# HCRT_STM32F103C8T6_Sch.net
KiCad netlist of a schematic drawn in Altium Designer
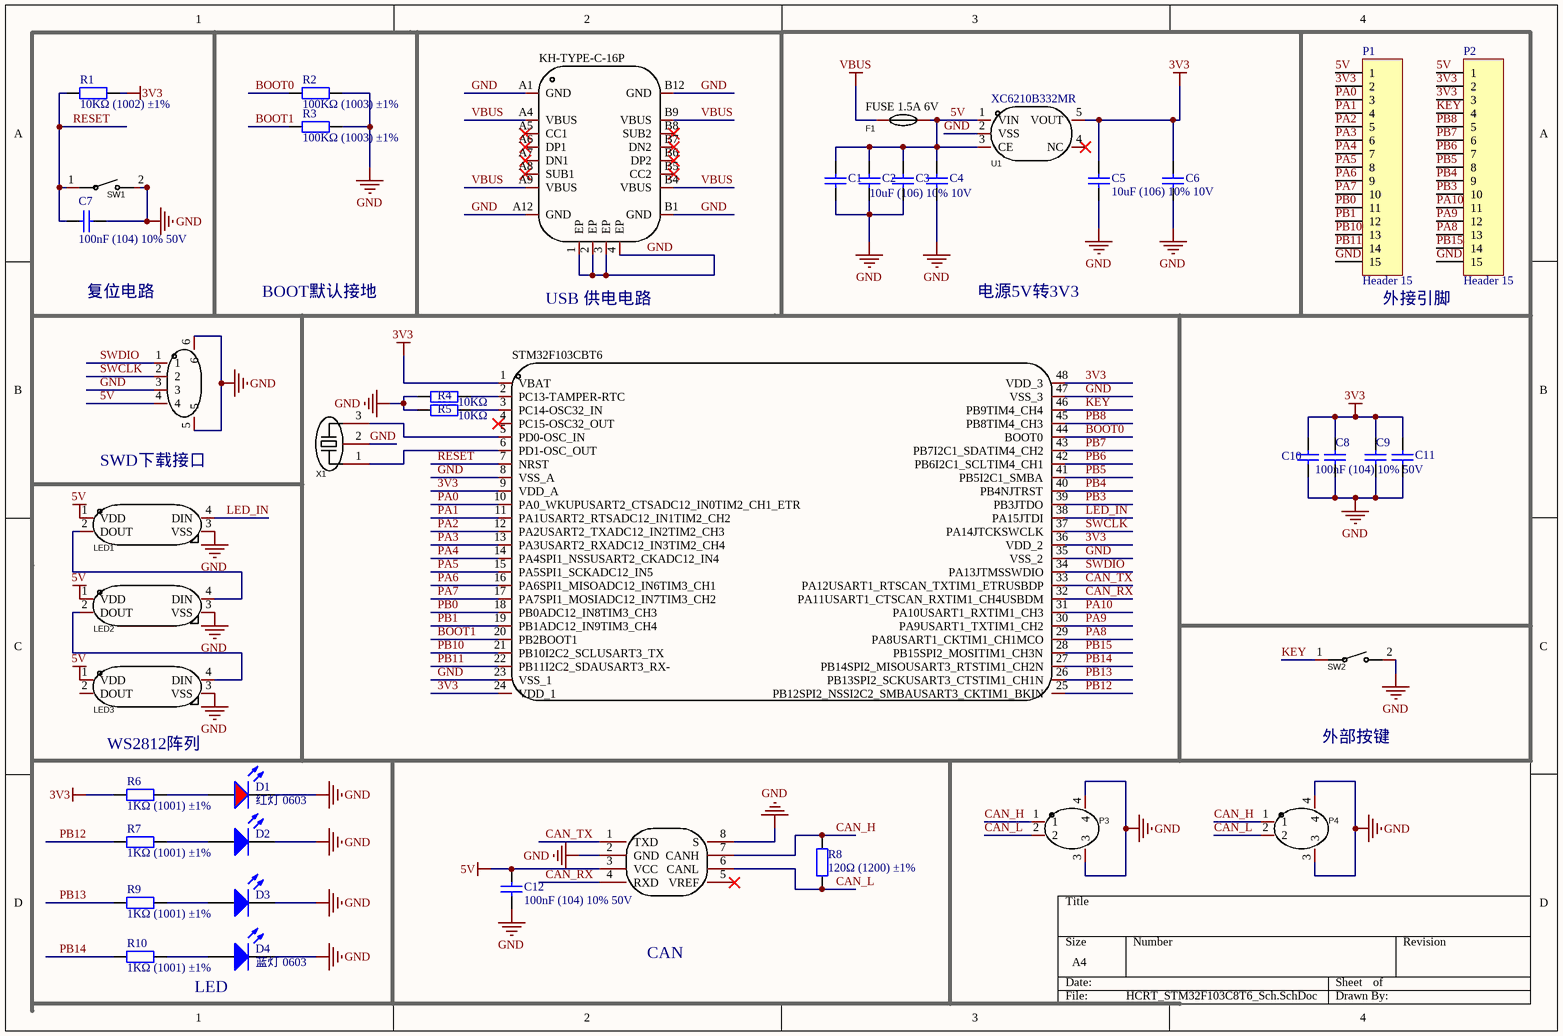
[diagram p0: HCRT_STM32F103C8T6_Sch.SchDoc]

(export (version "E")
  (design (tool "Eeschema 10.0.6"))
  (components
    (comp (ref "C1")
      (value "10uF (106) 10% 10V")
      (footprint "0603_C")
      (description "贴片电容")
      (libsource (lib "Miscellaneous Devices LC") (part "0603 10uF (106) 10% 10V"))
    )
    (comp (ref "C2")
      (value "10uF (106) 10% 10V")
      (footprint "0603_C")
      (description "贴片电容")
      (libsource (lib "Miscellaneous Devices LC") (part "0603 10uF (106) 10% 10V"))
    )
    (comp (ref "C3")
      (value "10uF (106) 10% 10V")
      (footprint "0603_C")
      (description "贴片电容")
      (libsource (lib "Miscellaneous Devices LC") (part "0603 10uF (106) 10% 10V"))
    )
    (comp (ref "C4")
      (value "10uF (106) 10% 10V")
      (footprint "0603_C")
      (description "贴片电容")
      (libsource (lib "Miscellaneous Devices LC") (part "0603 10uF (106) 10% 10V"))
    )
    (comp (ref "C5")
      (value "10uF (106) 10% 10V")
      (footprint "0603_C")
      (description "贴片电容")
      (libsource (lib "Miscellaneous Devices LC") (part "0603 10uF (106) 10% 10V"))
    )
    (comp (ref "C6")
      (value "10uF (106) 10% 10V")
      (footprint "0603_C")
      (description "贴片电容")
      (libsource (lib "Miscellaneous Devices LC") (part "0603 10uF (106) 10% 10V"))
    )
    (comp (ref "C7")
      (value "100nF (104) 10% 50V")
      (footprint "0603_C")
      (description "贴片电容")
      (libsource (lib "Miscellaneous Devices LC") (part "0603 100nF (104) 10% 50V"))
    )
    (comp (ref "C8")
      (value "100nF (104) 10% 50V")
      (footprint "0603_C")
      (description "贴片电容")
      (libsource (lib "Miscellaneous Devices LC") (part "0603 100nF (104) 10% 50V"))
    )
    (comp (ref "C9")
      (value "100nF (104) 10% 50V")
      (footprint "0603_C")
      (description "贴片电容")
      (libsource (lib "Miscellaneous Devices LC") (part "0603 100nF (104) 10% 50V"))
    )
    (comp (ref "C10")
      (value "100nF (104) 10% 50V")
      (footprint "0603_C")
      (description "贴片电容")
      (libsource (lib "Miscellaneous Devices LC") (part "0603 100nF (104) 10% 50V"))
    )
    (comp (ref "C11")
      (value "100nF (104) 10% 50V")
      (footprint "0603_C")
      (description "贴片电容")
      (libsource (lib "Miscellaneous Devices LC") (part "0603 100nF (104) 10% 50V"))
    )
    (comp (ref "C12")
      (value "100nF (104) 10% 50V")
      (footprint "0603_C")
      (description "贴片电容")
      (libsource (lib "Miscellaneous Devices LC") (part "0603 100nF (104) 10% 50V"))
    )
    (comp (ref "CN1")
      (value "HC-1.25-4PWT")
      (footprint "CONN-SMD_4P-P1.25-HC-1.25-4PWT")
      (fields (field (name "MANUFACTURER") "HCTL(华灿天禄)"))
      (libsource (lib "zxy's_LIB") (part "HC-1.25-4PWT"))
    )
    (comp (ref "D1")
      (value "红灯 0603")
      (footprint "0603_LED_S1")
      (description "发光二极管")
      (libsource (lib "Miscellaneous Devices LC") (part "0603 红灯"))
    )
    (comp (ref "D2")
      (value "蓝灯 0603")
      (footprint "0603_LED_S1")
      (description "发光二极管")
      (libsource (lib "Miscellaneous Devices LC") (part "0603 蓝灯"))
    )
    (comp (ref "D3")
      (value "蓝灯 0603")
      (footprint "0603_LED_S1")
      (description "发光二极管")
      (libsource (lib "Miscellaneous Devices LC") (part "0603 蓝灯"))
    )
    (comp (ref "D4")
      (value "蓝灯 0603")
      (footprint "0603_LED_S1")
      (description "发光二极管")
      (libsource (lib "Miscellaneous Devices LC") (part "0603 蓝灯"))
    )
    (comp (ref "F1")
      (value "FUSE0603")
      (footprint "F0603")
      (fields (field (name "MANUFACTURER") "BHFUSE(佰宏)") (field (name "MANUFACTURER PART") "BSMD0603L-150"))
      (libsource (lib "zxy's_LIB") (part "FUSE0603"))
    )
    (comp (ref "LED1")
      (value "WS2812C")
      (footprint "LED-SMD_4P-L5.0-W5.0-LS5.4-TL-1")
      (fields (field (name "MANUFACTURER") "worldsemi"))
      (libsource (lib "zxy's_LIB") (part "WS2812C"))
    )
    (comp (ref "LED2")
      (value "WS2812C")
      (footprint "LED-SMD_4P-L5.0-W5.0-LS5.4-TL-1")
      (fields (field (name "MANUFACTURER") "worldsemi"))
      (libsource (lib "zxy's_LIB") (part "WS2812C"))
    )
    (comp (ref "LED3")
      (value "WS2812C")
      (footprint "LED-SMD_4P-L5.0-W5.0-LS5.4-TL-1")
      (fields (field (name "MANUFACTURER") "worldsemi"))
      (libsource (lib "zxy's_LIB") (part "WS2812C"))
    )
    (comp (ref "P1")
      (value "Header 15")
      (footprint "HDR1X15")
      (description "Header, 15-Pin")
      (fields (field (name "PUBLISHER") "Altium Limited"))
      (libsource (lib "Miscellaneous Connectors") (part "Header 15"))
    )
    (comp (ref "P2")
      (value "Header 15")
      (footprint "HDR1X15")
      (description "Header, 15-Pin")
      (fields (field (name "PUBLISHER") "Altium Limited"))
      (libsource (lib "Miscellaneous Connectors") (part "Header 15"))
    )
    (comp (ref "P3")
      (value "1.25_2P")
      (footprint "CONN-SMD_SM02B-GHS-TB-LF-SN")
      (fields (field (name "MANUFACTURER") "JST") (field (name "MANUFACTURER PART") "SM02B-GHS-TB(LF)(SN)"))
      (libsource (lib "zxy's_LIB") (part "1.25_2P"))
    )
    (comp (ref "P4")
      (value "1.25_2P")
      (footprint "CONN-SMD_SM02B-GHS-TB-LF-SN")
      (fields (field (name "MANUFACTURER") "JST") (field (name "MANUFACTURER PART") "SM02B-GHS-TB(LF)(SN)"))
      (libsource (lib "zxy's_LIB") (part "1.25_2P"))
    )
    (comp (ref "R1")
      (value "10KΩ (1002) ±1%")
      (footprint "0603_R")
      (description "贴片电阻")
      (libsource (lib "Miscellaneous Devices LC") (part "0603 10KΩ (1002) 1%"))
    )
    (comp (ref "R2")
      (value "100KΩ (1003) ±1%")
      (footprint "0603_R")
      (description "贴片电阻")
      (libsource (lib "Miscellaneous Devices LC") (part "0603 100KΩ (1003) 1%"))
    )
    (comp (ref "R3")
      (value "100KΩ (1003) ±1%")
      (footprint "0603_R")
      (description "贴片电阻")
      (libsource (lib "Miscellaneous Devices LC") (part "0603 100KΩ (1003) 1%"))
    )
    (comp (ref "R4")
      (value "10KΩ")
      (footprint "0603_R")
      (description "贴片电阻")
      (libsource (lib "Miscellaneous Devices LC") (part "0603 10KΩ (1002) 1%"))
    )
    (comp (ref "R5")
      (value "10KΩ")
      (footprint "0603_R")
      (description "贴片电阻")
      (libsource (lib "Miscellaneous Devices LC") (part "0603 10KΩ (1002) 1%"))
    )
    (comp (ref "R6")
      (value "1KΩ (1001) ±1%")
      (footprint "0603_R")
      (description "贴片电阻")
      (libsource (lib "Miscellaneous Devices LC") (part "0603 1KΩ (1001) 1%"))
    )
    (comp (ref "R7")
      (value "1KΩ (1001) ±1%")
      (footprint "0603_R")
      (description "贴片电阻")
      (libsource (lib "Miscellaneous Devices LC") (part "0603 1KΩ (1001) 1%"))
    )
    (comp (ref "R8")
      (value "120Ω (1200) ±1%")
      (footprint "0603_R")
      (description "贴片电阻")
      (libsource (lib "Miscellaneous Devices LC") (part "0603 120Ω (1200) 1%"))
    )
    (comp (ref "R9")
      (value "1KΩ (1001) ±1%")
      (footprint "0603_R")
      (description "贴片电阻")
      (libsource (lib "Miscellaneous Devices LC") (part "0603 1KΩ (1001) 1%"))
    )
    (comp (ref "R10")
      (value "1KΩ (1001) ±1%")
      (footprint "0603_R")
      (description "贴片电阻")
      (libsource (lib "Miscellaneous Devices LC") (part "0603 1KΩ (1001) 1%"))
    )
    (comp (ref "SW1")
      (value "K2-1107ST-A4DW-06_C118141")
      (footprint "KEY-SMD_L6.2-W3.6-LS8.0")
      (fields (field (name "MANUFACTURER") "韩国韩荣") (field (name "MANUFACTURER PART") "K2-1107ST-A4DW-06"))
      (libsource (lib "zxy's_LIB") (part "K2-1107ST-A4DW-06_C118141"))
    )
    (comp (ref "SW2")
      (value "K2-1107ST-A4DW-06_C118141")
      (footprint "KEY-SMD_L6.2-W3.6-LS8.0")
      (fields (field (name "MANUFACTURER") "韩国韩荣") (field (name "MANUFACTURER PART") "K2-1107ST-A4DW-06"))
      (libsource (lib "zxy's_LIB") (part "K2-1107ST-A4DW-06_C118141"))
    )
    (comp (ref "U1")
      (value "XC6210B332MR")
      (footprint "SOT-23-5_L3.0-W1.7-P0.95-LS2.8-BR")
      (fields (field (name "MANUFACTURER") "TOREX(特瑞仕)"))
      (libsource (lib "zxy's_LIB") (part "XC6210B332MR"))
    )
    (comp (ref "U2")
      (value "STM32F103CBT6")
      (footprint "LQFP-48_L7.0-W7.0-P0.50-LS9.0-BL")
      (fields (field (name "MANUFACTURER") "ST(意法半导体)"))
      (libsource (lib "zxy's_LIB") (part "STM32F103CBT6"))
    )
    (comp (ref "U3")
      (value "TJA1050T/CM,118")
      (footprint "SOIC-8_L5.0-W4.0-P1.27-LS6.0-BL")
      (fields (field (name "MANUFACTURER") "NXP(恩智浦)"))
      (libsource (lib "zxy's_LIB") (part "TJA1050T/CM,118"))
    )
    (comp (ref "USB1")
      (value "KH-TYPE-C-16P")
      (footprint "USB-C-SMD_KH-TYPE-C-16P")
      (fields (field (name "MANUFACTURER") "kinghelm(金航标)"))
      (libsource (lib "zxy's_LIB") (part "KH-TYPE-C-16P"))
    )
    (comp (ref "X1")
      (value "CSTCE8M00G15C99-R0")
      (footprint "OSC-SMD_3P-L3.2-W1.3-P1.2-L")
      (fields (field (name "MANUFACTURER") "muRata(村田)"))
      (libsource (lib "zxy's_LIB") (part "CSTCE8M00G15C99-R0"))
    )
  )
  (nets
    (net (code "1") (name "/BOOT0") (class "Default")
      (node (ref "R2") (pin "1") (pinfunction "1_1") (pintype "passive"))
      (node (ref "U2") (pin "44") (pinfunction "BOOT0_44") (pintype "passive"))
    )
    (net (code "2") (name "/BOOT1") (class "Default")
      (node (ref "R3") (pin "1") (pinfunction "1_1") (pintype "passive"))
      (node (ref "U2") (pin "20") (pinfunction "PB2BOOT1_20") (pintype "passive"))
    )
    (net (code "3") (name "/CAN_H") (class "Default")
      (node (ref "P3") (pin "1") (pinfunction "1_1") (pintype "passive"))
      (node (ref "P4") (pin "1") (pinfunction "1_1") (pintype "passive"))
      (node (ref "R8") (pin "2") (pinfunction "2_2") (pintype "passive"))
      (node (ref "U3") (pin "7") (pinfunction "CANH_7") (pintype "passive"))
    )
    (net (code "4") (name "/CAN_L") (class "Default")
      (node (ref "P3") (pin "2") (pinfunction "2_2") (pintype "passive"))
      (node (ref "P4") (pin "2") (pinfunction "2_2") (pintype "passive"))
      (node (ref "R8") (pin "1") (pinfunction "1_1") (pintype "passive"))
      (node (ref "U3") (pin "6") (pinfunction "CANL_6") (pintype "passive"))
    )
    (net (code "5") (name "/CAN_RX") (class "Default")
      (node (ref "U2") (pin "32") (pinfunction "PA11USART1_CTSCAN_RXTIM1_CH4USBDM_32") (pintype "passive"))
      (node (ref "U3") (pin "4") (pinfunction "RXD_4") (pintype "passive"))
    )
    (net (code "6") (name "/CAN_TX") (class "Default")
      (node (ref "U2") (pin "33") (pinfunction "PA12USART1_RTSCAN_TXTIM1_ETRUSBDP_33") (pintype "passive"))
      (node (ref "U3") (pin "1") (pinfunction "TXD_1") (pintype "passive"))
    )
    (net (code "7") (name "/KEY") (class "Default")
      (node (ref "P2") (pin "4") (pinfunction "4_4") (pintype "passive"))
      (node (ref "SW2") (pin "1") (pinfunction "1_1") (pintype "passive"))
      (node (ref "U2") (pin "46") (pinfunction "PB9TIM4_CH4_46") (pintype "passive"))
    )
    (net (code "8") (name "/LED_IN") (class "Default")
      (node (ref "LED1") (pin "4") (pinfunction "DIN_4") (pintype "passive"))
      (node (ref "U2") (pin "38") (pinfunction "PA15JTDI_38") (pintype "passive"))
    )
    (net (code "9") (name "/PA0") (class "Default")
      (node (ref "P1") (pin "3") (pinfunction "3_3") (pintype "passive"))
      (node (ref "U2") (pin "10") (pinfunction "PA0_WKUPUSART2_CTSADC12_IN0TIM2_CH1_ETR_10") (pintype "passive"))
    )
    (net (code "10") (name "/PA1") (class "Default")
      (node (ref "P1") (pin "4") (pinfunction "4_4") (pintype "passive"))
      (node (ref "U2") (pin "11") (pinfunction "PA1USART2_RTSADC12_IN1TIM2_CH2_11") (pintype "passive"))
    )
    (net (code "11") (name "/PA2") (class "Default")
      (node (ref "P1") (pin "5") (pinfunction "5_5") (pintype "passive"))
      (node (ref "U2") (pin "12") (pinfunction "PA2USART2_TXADC12_IN2TIM2_CH3_12") (pintype "passive"))
    )
    (net (code "12") (name "/PA3") (class "Default")
      (node (ref "P1") (pin "6") (pinfunction "6_6") (pintype "passive"))
      (node (ref "U2") (pin "13") (pinfunction "PA3USART2_RXADC12_IN3TIM2_CH4_13") (pintype "passive"))
    )
    (net (code "13") (name "/PA4") (class "Default")
      (node (ref "P1") (pin "7") (pinfunction "7_7") (pintype "passive"))
      (node (ref "U2") (pin "14") (pinfunction "PA4SPI1_NSSUSART2_CKADC12_IN4_14") (pintype "passive"))
    )
    (net (code "14") (name "/PA5") (class "Default")
      (node (ref "P1") (pin "8") (pinfunction "8_8") (pintype "passive"))
      (node (ref "U2") (pin "15") (pinfunction "PA5SPI1_SCKADC12_IN5_15") (pintype "passive"))
    )
    (net (code "15") (name "/PA6") (class "Default")
      (node (ref "P1") (pin "9") (pinfunction "9_9") (pintype "passive"))
      (node (ref "U2") (pin "16") (pinfunction "PA6SPI1_MISOADC12_IN6TIM3_CH1_16") (pintype "passive"))
    )
    (net (code "16") (name "/PA7") (class "Default")
      (node (ref "P1") (pin "10") (pinfunction "10_10") (pintype "passive"))
      (node (ref "U2") (pin "17") (pinfunction "PA7SPI1_MOSIADC12_IN7TIM3_CH2_17") (pintype "passive"))
    )
    (net (code "17") (name "/PA8") (class "Default")
      (node (ref "P2") (pin "13") (pinfunction "13_13") (pintype "passive"))
      (node (ref "U2") (pin "29") (pinfunction "PA8USART1_CKTIM1_CH1MCO_29") (pintype "passive"))
    )
    (net (code "18") (name "/PA9") (class "Default")
      (node (ref "P2") (pin "12") (pinfunction "12_12") (pintype "passive"))
      (node (ref "U2") (pin "30") (pinfunction "PA9USART1_TXTIM1_CH2_30") (pintype "passive"))
    )
    (net (code "19") (name "/PA10") (class "Default")
      (node (ref "P2") (pin "11") (pinfunction "11_11") (pintype "passive"))
      (node (ref "U2") (pin "31") (pinfunction "PA10USART1_RXTIM1_CH3_31") (pintype "passive"))
    )
    (net (code "20") (name "/PB0") (class "Default")
      (node (ref "P1") (pin "11") (pinfunction "11_11") (pintype "passive"))
      (node (ref "U2") (pin "18") (pinfunction "PB0ADC12_IN8TIM3_CH3_18") (pintype "passive"))
    )
    (net (code "21") (name "/PB1") (class "Default")
      (node (ref "P1") (pin "12") (pinfunction "12_12") (pintype "passive"))
      (node (ref "U2") (pin "19") (pinfunction "PB1ADC12_IN9TIM3_CH4_19") (pintype "passive"))
    )
    (net (code "22") (name "/PB3") (class "Default")
      (node (ref "P2") (pin "10") (pinfunction "10_10") (pintype "passive"))
      (node (ref "U2") (pin "39") (pinfunction "PB3JTDO_39") (pintype "passive"))
    )
    (net (code "23") (name "/PB4") (class "Default")
      (node (ref "P2") (pin "9") (pinfunction "9_9") (pintype "passive"))
      (node (ref "U2") (pin "40") (pinfunction "PB4NJTRST_40") (pintype "passive"))
    )
    (net (code "24") (name "/PB5") (class "Default")
      (node (ref "P2") (pin "8") (pinfunction "8_8") (pintype "passive"))
      (node (ref "U2") (pin "41") (pinfunction "PB5I2C1_SMBA_41") (pintype "passive"))
    )
    (net (code "25") (name "/PB6") (class "Default")
      (node (ref "P2") (pin "7") (pinfunction "7_7") (pintype "passive"))
      (node (ref "U2") (pin "42") (pinfunction "PB6I2C1_SCLTIM4_CH1_42") (pintype "passive"))
    )
    (net (code "26") (name "/PB7") (class "Default")
      (node (ref "P2") (pin "6") (pinfunction "6_6") (pintype "passive"))
      (node (ref "U2") (pin "43") (pinfunction "PB7I2C1_SDATIM4_CH2_43") (pintype "passive"))
    )
    (net (code "27") (name "/PB8") (class "Default")
      (node (ref "P2") (pin "5") (pinfunction "5_5") (pintype "passive"))
      (node (ref "U2") (pin "45") (pinfunction "PB8TIM4_CH3_45") (pintype "passive"))
    )
    (net (code "28") (name "/PB10") (class "Default")
      (node (ref "P1") (pin "13") (pinfunction "13_13") (pintype "passive"))
      (node (ref "U2") (pin "21") (pinfunction "PB10I2C2_SCLUSART3_TX_21") (pintype "passive"))
    )
    (net (code "29") (name "/PB11") (class "Default")
      (node (ref "P1") (pin "14") (pinfunction "14_14") (pintype "passive"))
      (node (ref "U2") (pin "22") (pinfunction "PB11I2C2_SDAUSART3_RX-_22") (pintype "passive"))
    )
    (net (code "30") (name "/PB12") (class "Default")
      (node (ref "R7") (pin "1") (pinfunction "1_1") (pintype "passive"))
      (node (ref "U2") (pin "25") (pinfunction "PB12SPI2_NSSI2C2_SMBAUSART3_CKTIM1_BKIN_25") (pintype "passive"))
    )
    (net (code "31") (name "/PB13") (class "Default")
      (node (ref "R9") (pin "1") (pinfunction "1_1") (pintype "passive"))
      (node (ref "U2") (pin "26") (pinfunction "PB13SPI2_SCKUSART3_CTSTIM1_CH1N_26") (pintype "passive"))
    )
    (net (code "32") (name "/PB14") (class "Default")
      (node (ref "R10") (pin "1") (pinfunction "1_1") (pintype "passive"))
      (node (ref "U2") (pin "27") (pinfunction "PB14SPI2_MISOUSART3_RTSTIM1_CH2N_27") (pintype "passive"))
    )
    (net (code "33") (name "/PB15") (class "Default")
      (node (ref "P2") (pin "14") (pinfunction "14_14") (pintype "passive"))
      (node (ref "U2") (pin "28") (pinfunction "PB15SPI2_MOSITIM1_CH3N_28") (pintype "passive"))
    )
    (net (code "34") (name "/RESET") (class "Default")
      (node (ref "C7") (pin "1") (pinfunction "1_1") (pintype "passive"))
      (node (ref "R1") (pin "1") (pinfunction "1_1") (pintype "passive"))
      (node (ref "SW1") (pin "1") (pinfunction "1_1") (pintype "passive"))
      (node (ref "U2") (pin "7") (pinfunction "NRST_7") (pintype "passive"))
    )
    (net (code "35") (name "/SWCLK") (class "Default")
      (node (ref "CN1") (pin "2") (pinfunction "2_2") (pintype "passive"))
      (node (ref "U2") (pin "37") (pinfunction "PA14JTCKSWCLK_37") (pintype "passive"))
    )
    (net (code "36") (name "/SWDIO") (class "Default")
      (node (ref "CN1") (pin "1") (pinfunction "1_1") (pintype "passive"))
      (node (ref "U2") (pin "34") (pinfunction "PA13JTMSSWDIO_34") (pintype "passive"))
    )
    (net (code "37") (name "3V3") (class "Default")
      (node (ref "C10") (pin "2") (pinfunction "2_2") (pintype "passive"))
      (node (ref "C11") (pin "2") (pinfunction "2_2") (pintype "passive"))
      (node (ref "C5") (pin "2") (pinfunction "2_2") (pintype "passive"))
      (node (ref "C6") (pin "2") (pinfunction "2_2") (pintype "passive"))
      (node (ref "C8") (pin "2") (pinfunction "2_2") (pintype "passive"))
      (node (ref "C9") (pin "2") (pinfunction "2_2") (pintype "passive"))
      (node (ref "P1") (pin "2") (pinfunction "2_2") (pintype "passive"))
      (node (ref "P2") (pin "2") (pinfunction "2_2") (pintype "passive"))
      (node (ref "P2") (pin "3") (pinfunction "3_3") (pintype "passive"))
      (node (ref "R1") (pin "2") (pinfunction "2_2") (pintype "passive"))
      (node (ref "R6") (pin "1") (pinfunction "1_1") (pintype "passive"))
      (node (ref "U1") (pin "5") (pinfunction "VOUT_5") (pintype "passive"))
      (node (ref "U2") (pin "1") (pinfunction "VBAT_1") (pintype "passive"))
      (node (ref "U2") (pin "24") (pinfunction "VDD_1_24") (pintype "passive"))
      (node (ref "U2") (pin "36") (pinfunction "VDD_2_36") (pintype "passive"))
      (node (ref "U2") (pin "48") (pinfunction "VDD_3_48") (pintype "passive"))
      (node (ref "U2") (pin "9") (pinfunction "VDD_A_9") (pintype "passive"))
    )
    (net (code "38") (name "5V") (class "Default")
      (node (ref "C1") (pin "2") (pinfunction "2_2") (pintype "passive"))
      (node (ref "C12") (pin "2") (pinfunction "2_2") (pintype "passive"))
      (node (ref "C2") (pin "2") (pinfunction "2_2") (pintype "passive"))
      (node (ref "C3") (pin "2") (pinfunction "2_2") (pintype "passive"))
      (node (ref "C4") (pin "2") (pinfunction "2_2") (pintype "passive"))
      (node (ref "CN1") (pin "4") (pinfunction "4_4") (pintype "passive"))
      (node (ref "F1") (pin "2") (pinfunction "2_2") (pintype "passive"))
      (node (ref "LED1") (pin "1") (pinfunction "VDD_1") (pintype "passive"))
      (node (ref "LED2") (pin "1") (pinfunction "VDD_1") (pintype "passive"))
      (node (ref "LED3") (pin "1") (pinfunction "VDD_1") (pintype "passive"))
      (node (ref "P1") (pin "1") (pinfunction "1_1") (pintype "passive"))
      (node (ref "P2") (pin "1") (pinfunction "1_1") (pintype "passive"))
      (node (ref "U1") (pin "1") (pinfunction "VIN_1") (pintype "passive"))
      (node (ref "U1") (pin "3") (pinfunction "CE_3") (pintype "passive"))
      (node (ref "U3") (pin "3") (pinfunction "VCC_3") (pintype "passive"))
    )
    (net (code "39") (name "GND") (class "Default")
      (node (ref "C1") (pin "1") (pinfunction "1_1") (pintype "passive"))
      (node (ref "C10") (pin "1") (pinfunction "1_1") (pintype "passive"))
      (node (ref "C11") (pin "1") (pinfunction "1_1") (pintype "passive"))
      (node (ref "C12") (pin "1") (pinfunction "1_1") (pintype "passive"))
      (node (ref "C2") (pin "1") (pinfunction "1_1") (pintype "passive"))
      (node (ref "C3") (pin "1") (pinfunction "1_1") (pintype "passive"))
      (node (ref "C4") (pin "1") (pinfunction "1_1") (pintype "passive"))
      (node (ref "C5") (pin "1") (pinfunction "1_1") (pintype "passive"))
      (node (ref "C6") (pin "1") (pinfunction "1_1") (pintype "passive"))
      (node (ref "C7") (pin "2") (pinfunction "2_2") (pintype "passive"))
      (node (ref "C8") (pin "1") (pinfunction "1_1") (pintype "passive"))
      (node (ref "C9") (pin "1") (pinfunction "1_1") (pintype "passive"))
      (node (ref "CN1") (pin "3") (pinfunction "3_3") (pintype "passive"))
      (node (ref "CN1") (pin "5") (pinfunction "5_5") (pintype "passive"))
      (node (ref "CN1") (pin "6") (pinfunction "6_6") (pintype "passive"))
      (node (ref "D1") (pin "K") (pinfunction "K_K") (pintype "passive"))
      (node (ref "D2") (pin "K") (pinfunction "K_K") (pintype "passive"))
      (node (ref "D3") (pin "K") (pinfunction "K_K") (pintype "passive"))
      (node (ref "D4") (pin "K") (pinfunction "K_K") (pintype "passive"))
      (node (ref "LED1") (pin "3") (pinfunction "VSS_3") (pintype "passive"))
      (node (ref "LED2") (pin "3") (pinfunction "VSS_3") (pintype "passive"))
      (node (ref "LED3") (pin "3") (pinfunction "VSS_3") (pintype "passive"))
      (node (ref "P1") (pin "15") (pinfunction "15_15") (pintype "passive"))
      (node (ref "P2") (pin "15") (pinfunction "15_15") (pintype "passive"))
      (node (ref "P3") (pin "3") (pinfunction "3_3") (pintype "passive"))
      (node (ref "P3") (pin "4") (pinfunction "4_4") (pintype "passive"))
      (node (ref "P4") (pin "3") (pinfunction "3_3") (pintype "passive"))
      (node (ref "P4") (pin "4") (pinfunction "4_4") (pintype "passive"))
      (node (ref "R2") (pin "2") (pinfunction "2_2") (pintype "passive"))
      (node (ref "R3") (pin "2") (pinfunction "2_2") (pintype "passive"))
      (node (ref "R4") (pin "1") (pinfunction "1_1") (pintype "passive"))
      (node (ref "R5") (pin "1") (pinfunction "1_1") (pintype "passive"))
      (node (ref "SW1") (pin "2") (pinfunction "2_2") (pintype "passive"))
      (node (ref "SW2") (pin "2") (pinfunction "2_2") (pintype "passive"))
      (node (ref "U1") (pin "2") (pinfunction "VSS_2") (pintype "passive"))
      (node (ref "U2") (pin "23") (pinfunction "VSS_1_23") (pintype "passive"))
      (node (ref "U2") (pin "35") (pinfunction "VSS_2_35") (pintype "passive"))
      (node (ref "U2") (pin "47") (pinfunction "VSS_3_47") (pintype "passive"))
      (node (ref "U2") (pin "8") (pinfunction "VSS_A_8") (pintype "passive"))
      (node (ref "U3") (pin "2") (pinfunction "GND_2") (pintype "passive"))
      (node (ref "U3") (pin "8") (pinfunction "S_8") (pintype "passive"))
      (node (ref "USB1") (pin "1") (pinfunction "EP_1") (pintype "passive"))
      (node (ref "USB1") (pin "2") (pinfunction "EP_2") (pintype "passive"))
      (node (ref "USB1") (pin "3") (pinfunction "EP_3") (pintype "passive"))
      (node (ref "USB1") (pin "4") (pinfunction "EP_4") (pintype "passive"))
      (node (ref "USB1") (pin "A1") (pinfunction "GND_A1") (pintype "passive"))
      (node (ref "USB1") (pin "A12") (pinfunction "GND_A12") (pintype "passive"))
      (node (ref "USB1") (pin "B1") (pinfunction "GND_B1") (pintype "passive"))
      (node (ref "USB1") (pin "B12") (pinfunction "GND_B12") (pintype "passive"))
      (node (ref "X1") (pin "2") (pinfunction "2_2") (pintype "passive"))
    )
    (net (code "40") (name "Net-(D1-PadA)") (class "Default")
      (node (ref "D1") (pin "A") (pinfunction "A_A") (pintype "passive"))
      (node (ref "R6") (pin "2") (pinfunction "2_2") (pintype "passive"))
    )
    (net (code "41") (name "Net-(D2-PadA)") (class "Default")
      (node (ref "D2") (pin "A") (pinfunction "A_A") (pintype "passive"))
      (node (ref "R7") (pin "2") (pinfunction "2_2") (pintype "passive"))
    )
    (net (code "42") (name "Net-(D3-PadA)") (class "Default")
      (node (ref "D3") (pin "A") (pinfunction "A_A") (pintype "passive"))
      (node (ref "R9") (pin "2") (pinfunction "2_2") (pintype "passive"))
    )
    (net (code "43") (name "Net-(D4-PadA)") (class "Default")
      (node (ref "D4") (pin "A") (pinfunction "A_A") (pintype "passive"))
      (node (ref "R10") (pin "2") (pinfunction "2_2") (pintype "passive"))
    )
    (net (code "44") (name "Net-(LED1-DOUT)") (class "Default")
      (node (ref "LED1") (pin "2") (pinfunction "DOUT_2") (pintype "passive"))
      (node (ref "LED2") (pin "4") (pinfunction "DIN_4") (pintype "passive"))
    )
    (net (code "45") (name "Net-(LED2-DOUT)") (class "Default")
      (node (ref "LED2") (pin "2") (pinfunction "DOUT_2") (pintype "passive"))
      (node (ref "LED3") (pin "4") (pinfunction "DIN_4") (pintype "passive"))
    )
    (net (code "46") (name "Net-(U2-PC13-TAMPER-RTC)") (class "Default")
      (node (ref "R4") (pin "2") (pinfunction "2_2") (pintype "passive"))
      (node (ref "U2") (pin "2") (pinfunction "PC13-TAMPER-RTC_2") (pintype "passive"))
    )
    (net (code "47") (name "Net-(U2-PC14-OSC32_IN)") (class "Default")
      (node (ref "R5") (pin "2") (pinfunction "2_2") (pintype "passive"))
      (node (ref "U2") (pin "3") (pinfunction "PC14-OSC32_IN_3") (pintype "passive"))
    )
    (net (code "48") (name "Net-(U2-PD0-OSC_IN)") (class "Default")
      (node (ref "U2") (pin "5") (pinfunction "PD0-OSC_IN_5") (pintype "passive"))
      (node (ref "X1") (pin "3") (pinfunction "3_3") (pintype "passive"))
    )
    (net (code "49") (name "Net-(U2-PD1-OSC_OUT)") (class "Default")
      (node (ref "U2") (pin "6") (pinfunction "PD1-OSC_OUT_6") (pintype "passive"))
      (node (ref "X1") (pin "1") (pinfunction "1_1") (pintype "passive"))
    )
    (net (code "50") (name "VBUS") (class "Default")
      (node (ref "F1") (pin "1") (pinfunction "1_1") (pintype "passive"))
      (node (ref "USB1") (pin "A4") (pinfunction "VBUS_A4") (pintype "passive"))
      (node (ref "USB1") (pin "A9") (pinfunction "VBUS_A9") (pintype "passive"))
      (node (ref "USB1") (pin "B4") (pinfunction "VBUS_B4") (pintype "passive"))
      (node (ref "USB1") (pin "B9") (pinfunction "VBUS_B9") (pintype "passive"))
    )
    (net (code "51") (name "unconnected-(LED3-DOUT-Pad2)") (class "Default")
      (node (ref "LED3") (pin "2") (pinfunction "DOUT_2") (pintype "passive"))
    )
    (net (code "52") (name "unconnected-(U1-NC-Pad4)") (class "Default")
      (node (ref "U1") (pin "4") (pinfunction "NC_4") (pintype "passive+no_connect"))
    )
    (net (code "53") (name "unconnected-(U2-PC15-OSC32_OUT-Pad4)") (class "Default")
      (node (ref "U2") (pin "4") (pinfunction "PC15-OSC32_OUT_4") (pintype "passive+no_connect"))
    )
    (net (code "54") (name "unconnected-(U3-VREF-Pad5)") (class "Default")
      (node (ref "U3") (pin "5") (pinfunction "VREF_5") (pintype "passive+no_connect"))
    )
    (net (code "55") (name "unconnected-(USB1-CC1-PadA5)") (class "Default")
      (node (ref "USB1") (pin "A5") (pinfunction "CC1_A5") (pintype "passive+no_connect"))
    )
    (net (code "56") (name "unconnected-(USB1-CC2-PadB5)") (class "Default")
      (node (ref "USB1") (pin "B5") (pinfunction "CC2_B5") (pintype "passive+no_connect"))
    )
    (net (code "57") (name "unconnected-(USB1-DN1-PadA7)") (class "Default")
      (node (ref "USB1") (pin "A7") (pinfunction "DN1_A7") (pintype "passive+no_connect"))
    )
    (net (code "58") (name "unconnected-(USB1-DN2-PadB7)") (class "Default")
      (node (ref "USB1") (pin "B7") (pinfunction "DN2_B7") (pintype "passive+no_connect"))
    )
    (net (code "59") (name "unconnected-(USB1-DP1-PadA6)") (class "Default")
      (node (ref "USB1") (pin "A6") (pinfunction "DP1_A6") (pintype "passive+no_connect"))
    )
    (net (code "60") (name "unconnected-(USB1-DP2-PadB6)") (class "Default")
      (node (ref "USB1") (pin "B6") (pinfunction "DP2_B6") (pintype "passive+no_connect"))
    )
    (net (code "61") (name "unconnected-(USB1-SUB1-PadA8)") (class "Default")
      (node (ref "USB1") (pin "A8") (pinfunction "SUB1_A8") (pintype "passive+no_connect"))
    )
    (net (code "62") (name "unconnected-(USB1-SUB2-PadB8)") (class "Default")
      (node (ref "USB1") (pin "B8") (pinfunction "SUB2_B8") (pintype "passive+no_connect"))
    )
  )
)
